# SCH_Bear-circuit_2025-11-09.net
KiCad netlist of a schematic drawn in EasyEDA
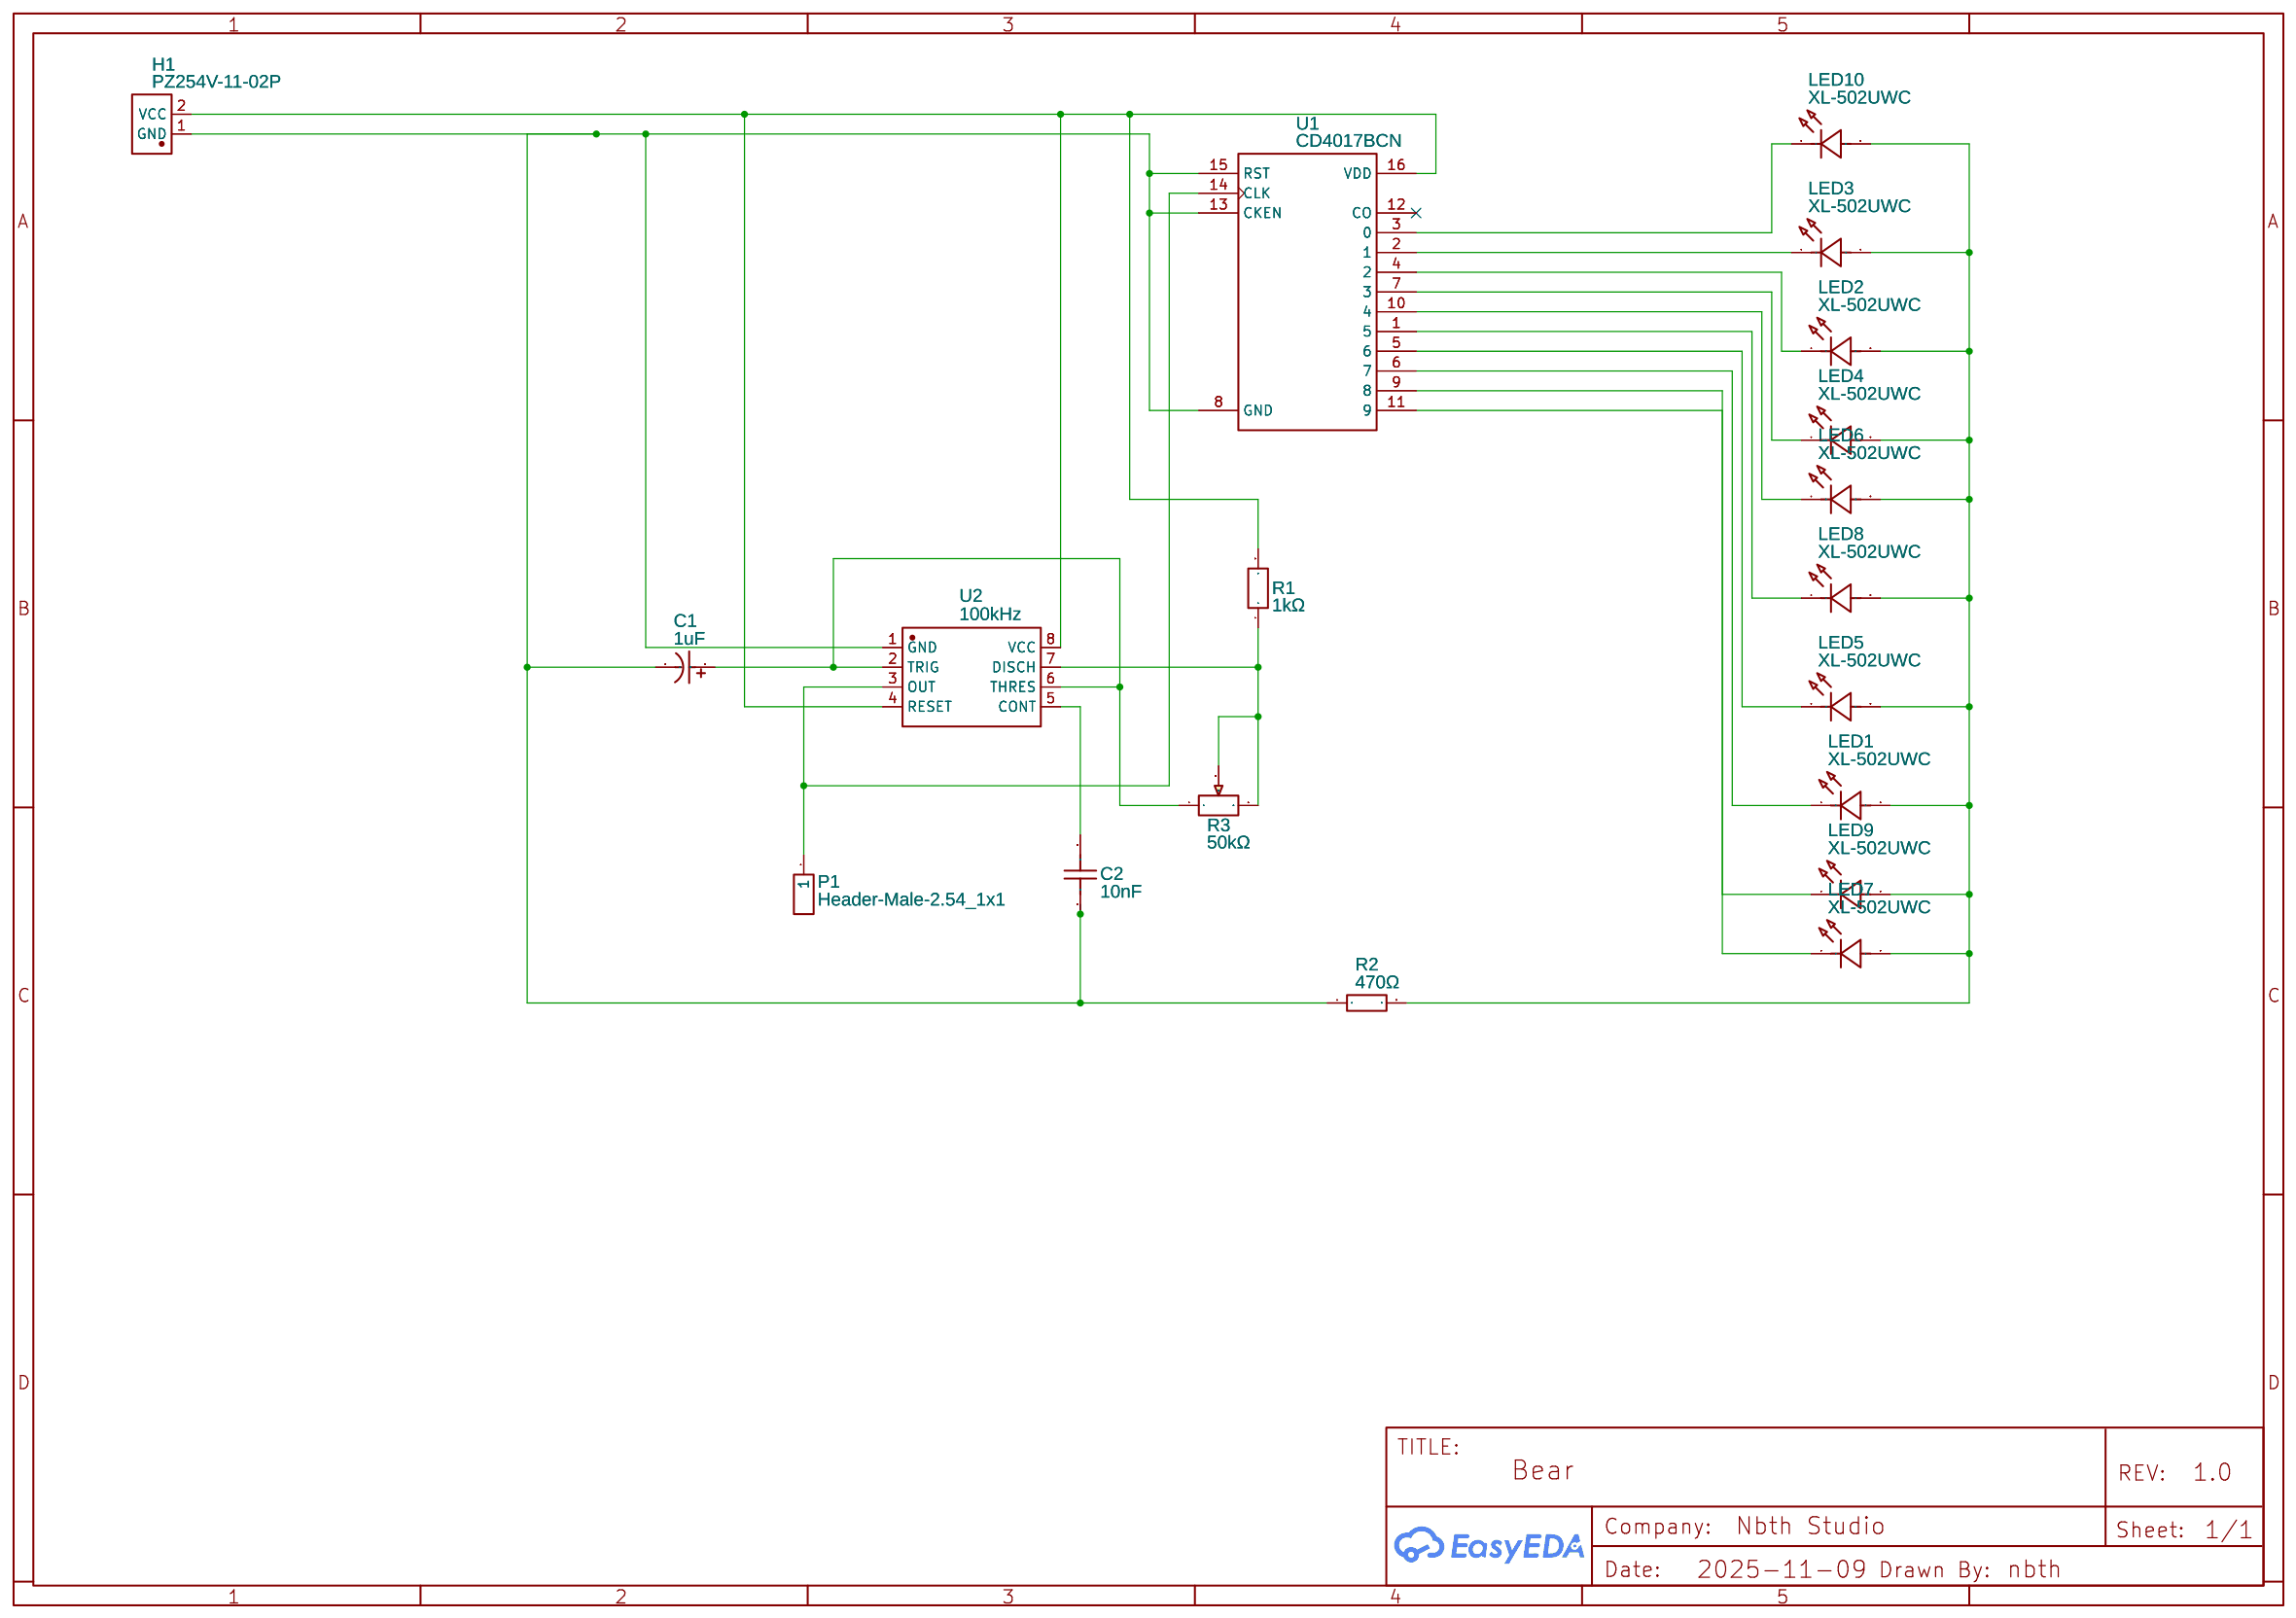
[diagram p0: schematic sheet]

(export (version "E")
  (design (tool "Eeschema 10.0.6"))
  (components
    (comp (ref "C1")
      (value "1uF")
      (fields (field (name "Manufacturer Part") "KF010M050C110A") (field (name "Manufacturer") "CapXon(丰宾)"))
      (libsource (lib "") (part "KF010M050C110A"))
    )
    (comp (ref "C2")
      (value "10nF")
      (fields (field (name "Manufacturer Part") "N09F1B103MN0B0S0N0") (field (name "Manufacturer") "STE(松田)"))
      (libsource (lib "") (part "N09F1B103MN0B0S0N0"))
    )
    (comp (ref "H1")
      (value "PZ254V-11-02P")
      (fields (field (name "Manufacturer") "XFCN(兴飞)"))
      (libsource (lib "") (part "PZ254V-11-02P"))
    )
    (comp (ref "LED1")
      (value "XL-502UWC")
      (fields (field (name "Manufacturer") "XINGLIGHT(成兴光)"))
      (libsource (lib "") (part "XL-502UWC"))
    )
    (comp (ref "LED2")
      (value "XL-502UWC")
      (fields (field (name "Manufacturer") "XINGLIGHT(成兴光)"))
      (libsource (lib "") (part "XL-502UWC"))
    )
    (comp (ref "LED3")
      (value "XL-502UWC")
      (fields (field (name "Manufacturer") "XINGLIGHT(成兴光)"))
      (libsource (lib "") (part "XL-502UWC"))
    )
    (comp (ref "LED4")
      (value "XL-502UWC")
      (fields (field (name "Manufacturer") "XINGLIGHT(成兴光)"))
      (libsource (lib "") (part "XL-502UWC"))
    )
    (comp (ref "LED5")
      (value "XL-502UWC")
      (fields (field (name "Manufacturer") "XINGLIGHT(成兴光)"))
      (libsource (lib "") (part "XL-502UWC"))
    )
    (comp (ref "LED6")
      (value "XL-502UWC")
      (fields (field (name "Manufacturer") "XINGLIGHT(成兴光)"))
      (libsource (lib "") (part "XL-502UWC"))
    )
    (comp (ref "LED7")
      (value "XL-502UWC")
      (fields (field (name "Manufacturer") "XINGLIGHT(成兴光)"))
      (libsource (lib "") (part "XL-502UWC"))
    )
    (comp (ref "LED8")
      (value "XL-502UWC")
      (fields (field (name "Manufacturer") "XINGLIGHT(成兴光)"))
      (libsource (lib "") (part "XL-502UWC"))
    )
    (comp (ref "LED9")
      (value "XL-502UWC")
      (fields (field (name "Manufacturer") "XINGLIGHT(成兴光)"))
      (libsource (lib "") (part "XL-502UWC"))
    )
    (comp (ref "LED10")
      (value "XL-502UWC")
      (fields (field (name "Manufacturer") "XINGLIGHT(成兴光)"))
      (libsource (lib "") (part "XL-502UWC"))
    )
    (comp (ref "P1")
      (value "Header-Male-2.54_1x1")
      (fields (field (name "Manufacturer Part") "2.54-1*1P针") (field (name "Manufacturer") "BOOMELE(博穆精密)"))
      (libsource (lib "") (part "Header-Male-2.54_1x1"))
    )
    (comp (ref "R1")
      (value "1kΩ")
      (fields (field (name "Manufacturer Part") "MF1/4W-1KΩ±1%T52") (field (name "Manufacturer") "华星机电"))
      (libsource (lib "") (part "MF1/4W-1KΩ±1%T52"))
    )
    (comp (ref "R2")
      (value "470Ω")
      (fields
        (field (name "Manufacturer Part") "MFR0W4F4700A50")
        (field (name "Manufacturer") "UNI-ROYAL(厚声)")
      )
      (libsource (lib "") (part "MFR0W4F4700A50"))
    )
    (comp (ref "R3")
      (value "50kΩ")
      (fields (field (name "Manufacturer Part") "3296X-1-503") (field (name "Manufacturer") "BOCHEN(博晨)"))
      (libsource (lib "") (part "3296X-1-503_C118912"))
    )
    (comp (ref "U1") (value "CD4017BCN") (libsource (lib "") (part "CD4017BCN")))
    (comp (ref "U2")
      (value "100kHz")
      (fields (field (name "Manufacturer Part") "NE555P") (field (name "Manufacturer") "TI(德州仪器)"))
      (libsource (lib "") (part "NE555P"))
    )
  )
  (nets
    (net (code "1") (name "Net-(H1-GND)") (class "Default")
      (node (ref "C1") (pin "2") (pinfunction "2_2") (pintype "input"))
      (node (ref "C2") (pin "1") (pinfunction "1_1") (pintype "unspecified"))
      (node (ref "H1") (pin "1") (pinfunction "GND_1") (pintype "unspecified"))
      (node (ref "R2") (pin "1") (pinfunction "1_1") (pintype "input"))
      (node (ref "U1") (pin "13") (pinfunction "CKEN_13") (pintype "unspecified"))
      (node (ref "U1") (pin "15") (pinfunction "RST_15") (pintype "unspecified"))
      (node (ref "U1") (pin "8") (pinfunction "GND_8") (pintype "passive"))
      (node (ref "U2") (pin "1") (pinfunction "GND_1") (pintype "unspecified"))
    )
    (net (code "2") (name "Net-(H1-VCC)") (class "Default")
      (node (ref "H1") (pin "2") (pinfunction "VCC_2") (pintype "unspecified"))
      (node (ref "R1") (pin "2") (pinfunction "2_2") (pintype "unspecified"))
      (node (ref "U1") (pin "16") (pinfunction "VDD_16") (pintype "passive"))
      (node (ref "U2") (pin "4") (pinfunction "RESET_4") (pintype "unspecified"))
      (node (ref "U2") (pin "8") (pinfunction "VCC_8") (pintype "unspecified"))
    )
    (net (code "3") (name "Net-(LED1-A)") (class "Default")
      (node (ref "LED1") (pin "2") (pinfunction "A_2") (pintype "unspecified"))
      (node (ref "LED10") (pin "2") (pinfunction "A_2") (pintype "unspecified"))
      (node (ref "LED2") (pin "2") (pinfunction "A_2") (pintype "unspecified"))
      (node (ref "LED3") (pin "2") (pinfunction "A_2") (pintype "unspecified"))
      (node (ref "LED4") (pin "2") (pinfunction "A_2") (pintype "unspecified"))
      (node (ref "LED5") (pin "2") (pinfunction "A_2") (pintype "unspecified"))
      (node (ref "LED6") (pin "2") (pinfunction "A_2") (pintype "unspecified"))
      (node (ref "LED7") (pin "2") (pinfunction "A_2") (pintype "unspecified"))
      (node (ref "LED8") (pin "2") (pinfunction "A_2") (pintype "unspecified"))
      (node (ref "LED9") (pin "2") (pinfunction "A_2") (pintype "unspecified"))
      (node (ref "R2") (pin "2") (pinfunction "2_2") (pintype "input"))
    )
    (net (code "4") (name "Net-(LED1-K)") (class "Default")
      (node (ref "LED1") (pin "1") (pinfunction "K_1") (pintype "unspecified"))
      (node (ref "U1") (pin "6") (pinfunction "7_6") (pintype "output"))
    )
    (net (code "5") (name "Net-(LED2-K)") (class "Default")
      (node (ref "LED2") (pin "1") (pinfunction "K_1") (pintype "unspecified"))
      (node (ref "U1") (pin "4") (pinfunction "2_4") (pintype "output"))
    )
    (net (code "6") (name "Net-(LED3-K)") (class "Default")
      (node (ref "LED3") (pin "1") (pinfunction "K_1") (pintype "unspecified"))
      (node (ref "U1") (pin "2") (pinfunction "1_2") (pintype "output"))
    )
    (net (code "7") (name "Net-(LED4-K)") (class "Default")
      (node (ref "LED4") (pin "1") (pinfunction "K_1") (pintype "unspecified"))
      (node (ref "U1") (pin "7") (pinfunction "3_7") (pintype "output"))
    )
    (net (code "8") (name "Net-(LED5-K)") (class "Default")
      (node (ref "LED5") (pin "1") (pinfunction "K_1") (pintype "unspecified"))
      (node (ref "U1") (pin "5") (pinfunction "6_5") (pintype "output"))
    )
    (net (code "9") (name "Net-(LED6-K)") (class "Default")
      (node (ref "LED6") (pin "1") (pinfunction "K_1") (pintype "unspecified"))
      (node (ref "U1") (pin "10") (pinfunction "4_10") (pintype "output"))
    )
    (net (code "10") (name "Net-(LED7-K)") (class "Default")
      (node (ref "LED7") (pin "1") (pinfunction "K_1") (pintype "unspecified"))
      (node (ref "U1") (pin "11") (pinfunction "9_11") (pintype "output"))
    )
    (net (code "11") (name "Net-(LED8-K)") (class "Default")
      (node (ref "LED8") (pin "1") (pinfunction "K_1") (pintype "unspecified"))
      (node (ref "U1") (pin "1") (pinfunction "5_1") (pintype "output"))
    )
    (net (code "12") (name "Net-(LED9-K)") (class "Default")
      (node (ref "LED9") (pin "1") (pinfunction "K_1") (pintype "unspecified"))
      (node (ref "U1") (pin "9") (pinfunction "8_9") (pintype "output"))
    )
    (net (code "13") (name "Net-(LED10-K)") (class "Default")
      (node (ref "LED10") (pin "1") (pinfunction "K_1") (pintype "unspecified"))
      (node (ref "U1") (pin "3") (pinfunction "0_3") (pintype "output"))
    )
    (net (code "14") (name "Net-(U1-CLK)") (class "Default")
      (node (ref "P1") (pin "1") (pinfunction "1_1") (pintype "input"))
      (node (ref "U1") (pin "14") (pinfunction "CLK_14") (pintype "unspecified"))
      (node (ref "U2") (pin "3") (pinfunction "OUT_3") (pintype "unspecified"))
    )
    (net (code "15") (name "Net-(U2-CONT)") (class "Default")
      (node (ref "C2") (pin "2") (pinfunction "2_2") (pintype "unspecified"))
      (node (ref "U2") (pin "5") (pinfunction "CONT_5") (pintype "unspecified"))
    )
    (net (code "16") (name "Net-(U2-DISCH)") (class "Default")
      (node (ref "R1") (pin "1") (pinfunction "1_1") (pintype "unspecified"))
      (node (ref "R3") (pin "2") (pinfunction "2_2") (pintype "input"))
      (node (ref "R3") (pin "3") (pinfunction "3_3") (pintype "input"))
      (node (ref "U2") (pin "7") (pinfunction "DISCH_7") (pintype "unspecified"))
    )
    (net (code "17") (name "Net-(U2-THRES)") (class "Default")
      (node (ref "C1") (pin "1") (pinfunction "1_1") (pintype "input"))
      (node (ref "R3") (pin "1") (pinfunction "1_1") (pintype "input"))
      (node (ref "U2") (pin "2") (pinfunction "TRIG_2") (pintype "unspecified"))
      (node (ref "U2") (pin "6") (pinfunction "THRES_6") (pintype "unspecified"))
    )
    (net (code "18") (name "unconnected-(U1-CO-Pad12)") (class "Default")
      (node (ref "U1") (pin "12") (pinfunction "CO_12") (pintype "output+no_connect"))
    )
  )
)
